# 04_-_LCD_VGA.net
KiCad netlist of a schematic drawn in Altium Designer
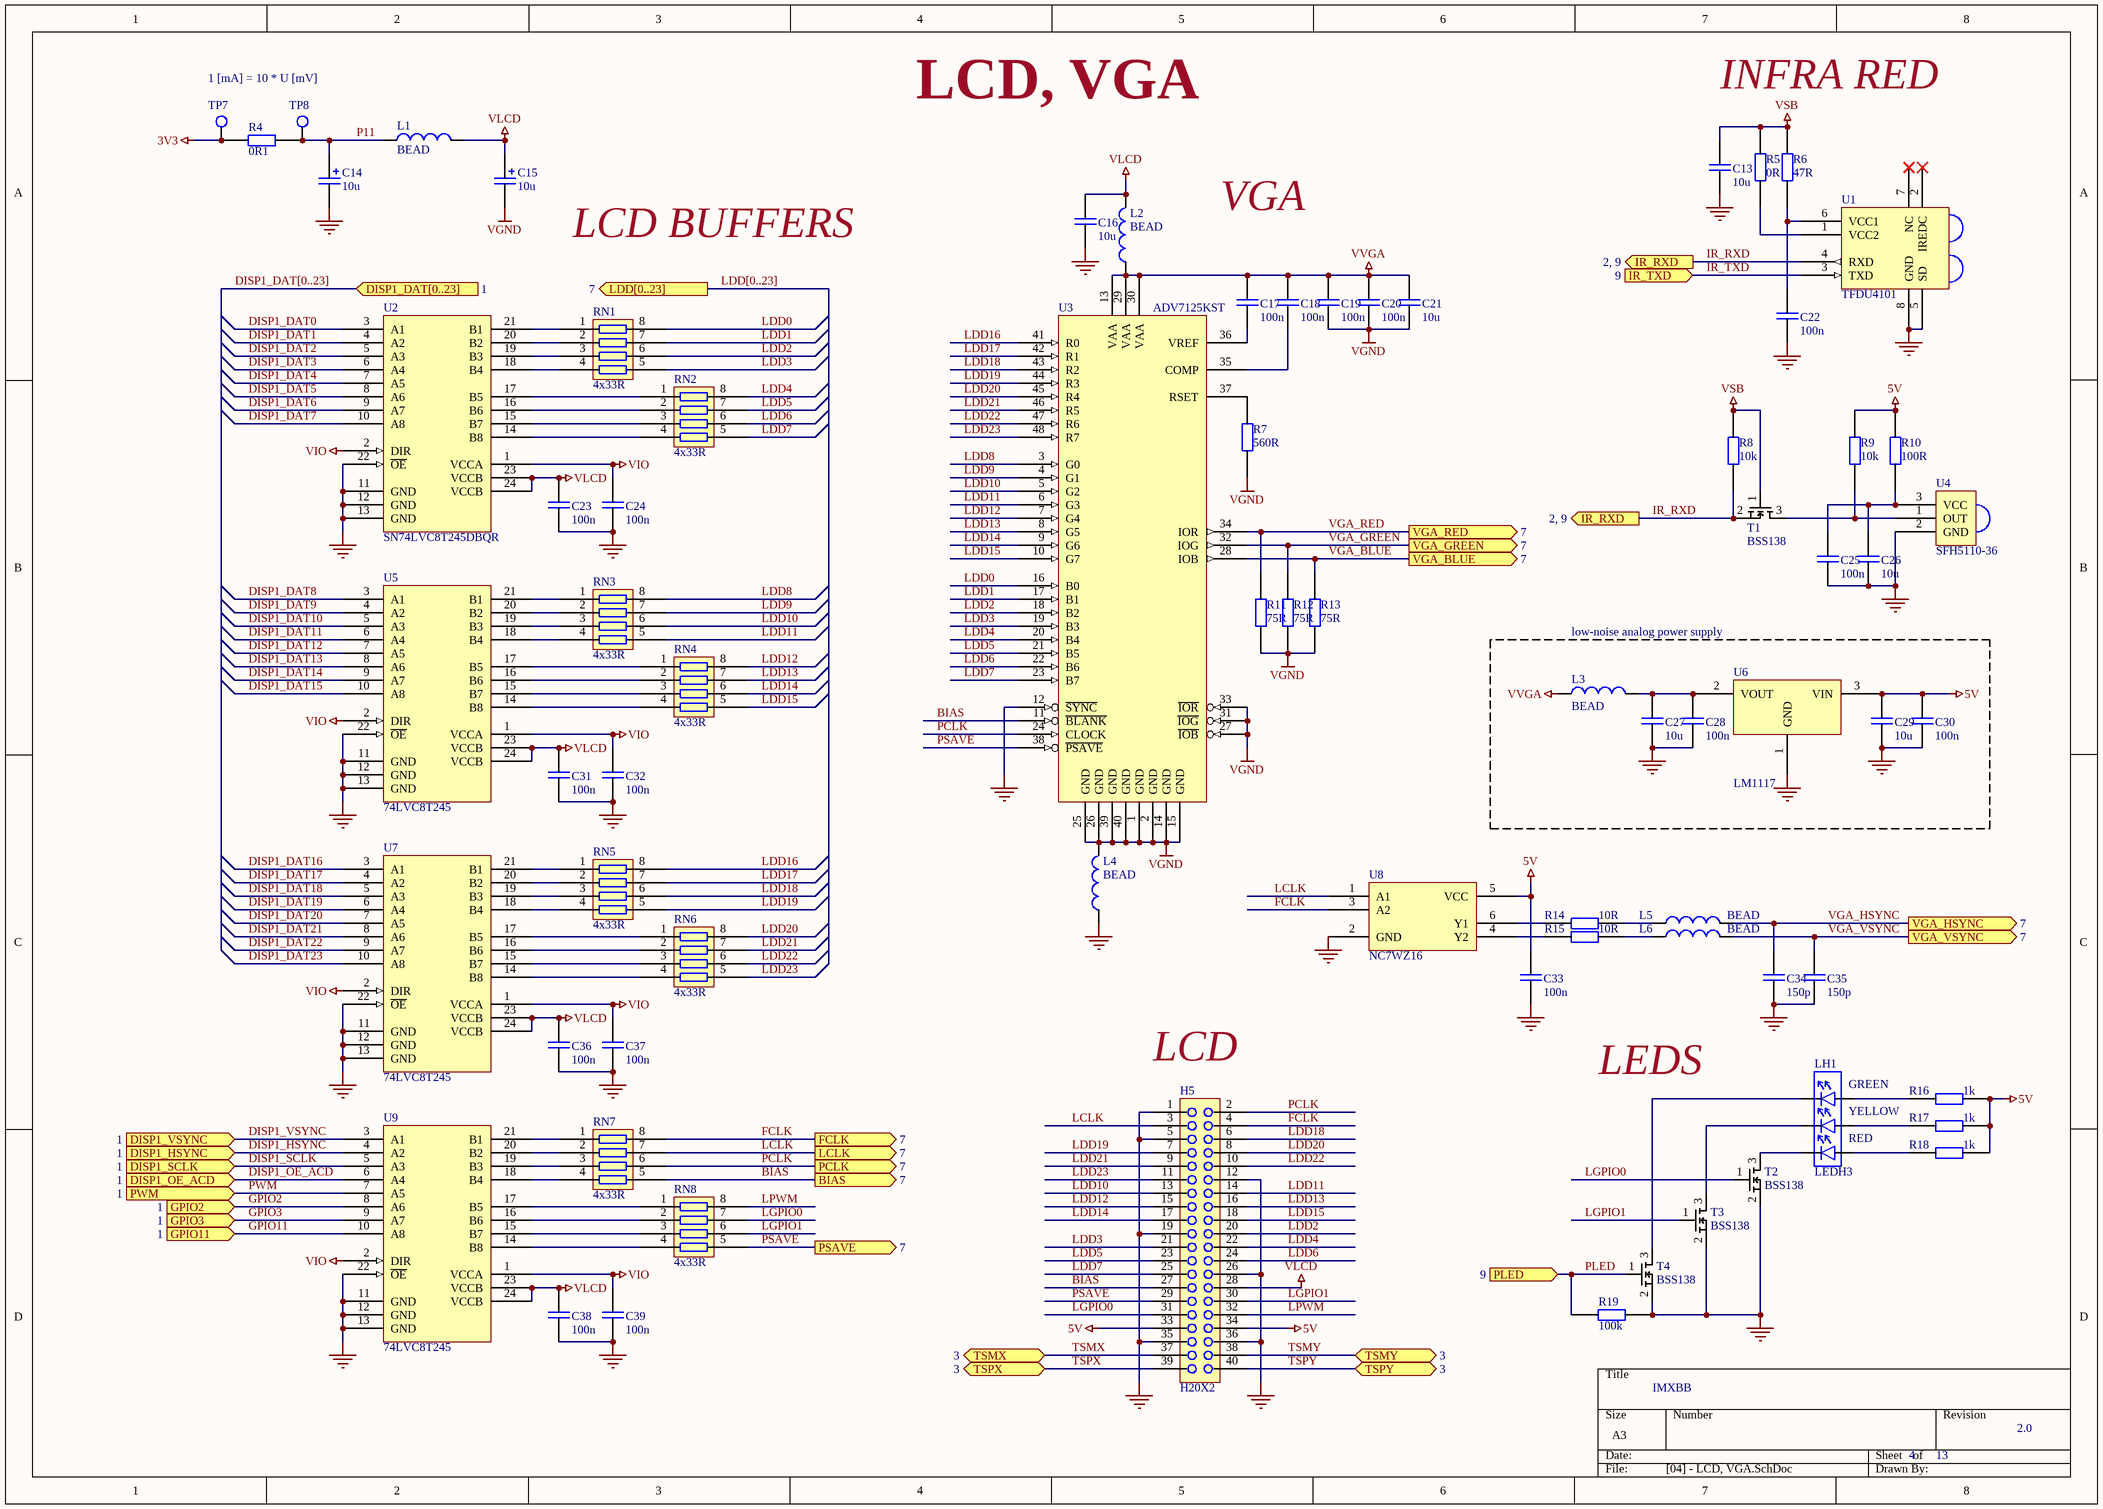
[diagram p0: [04] - LCD, VGA.SchDoc]

(export (version "E")
  (design (tool "Eeschema 10.0.6"))
  (components
    (comp (ref "C13") (value "10u") (footprint "0805") (libsource (lib "imxbb") (part "C")))
    (comp (ref "C14") (value "10u") (footprint "3216A") (libsource (lib "imxbb") (part "C+")))
    (comp (ref "C15") (value "10u") (footprint "3216A") (libsource (lib "imxbb") (part "C+")))
    (comp (ref "C16") (value "10u") (footprint "0805") (libsource (lib "imxbb") (part "C")))
    (comp (ref "C17") (value "100n") (footprint "0603") (libsource (lib "imxbb") (part "C")))
    (comp (ref "C18") (value "100n") (footprint "0603") (libsource (lib "imxbb") (part "C")))
    (comp (ref "C19") (value "100n") (footprint "0603") (libsource (lib "imxbb") (part "C")))
    (comp (ref "C20") (value "100n") (footprint "0603") (libsource (lib "imxbb") (part "C")))
    (comp (ref "C21") (value "10u") (footprint "0805") (libsource (lib "imxbb") (part "C")))
    (comp (ref "C22") (value "100n") (footprint "0603") (libsource (lib "imxbb") (part "C")))
    (comp (ref "C23") (value "100n") (footprint "0603") (libsource (lib "imxbb") (part "C")))
    (comp (ref "C24") (value "100n") (footprint "0603") (libsource (lib "imxbb") (part "C")))
    (comp (ref "C25") (value "100n") (footprint "0603") (libsource (lib "imxbb") (part "C")))
    (comp (ref "C26") (value "10u") (footprint "0805") (libsource (lib "imxbb") (part "C")))
    (comp (ref "C27") (value "10u") (footprint "0805") (libsource (lib "imxbb") (part "C")))
    (comp (ref "C28") (value "100n") (footprint "0603") (libsource (lib "imxbb") (part "C")))
    (comp (ref "C29") (value "10u") (footprint "0805") (libsource (lib "imxbb") (part "C")))
    (comp (ref "C30") (value "100n") (footprint "0603") (libsource (lib "imxbb") (part "C")))
    (comp (ref "C31") (value "100n") (footprint "0603") (libsource (lib "imxbb") (part "C")))
    (comp (ref "C32") (value "100n") (footprint "0603") (libsource (lib "imxbb") (part "C")))
    (comp (ref "C33") (value "100n") (footprint "0603") (libsource (lib "imxbb") (part "C")))
    (comp (ref "C34") (value "150p") (footprint "0603") (libsource (lib "imxbb") (part "C")))
    (comp (ref "C35") (value "150p") (footprint "0603") (libsource (lib "imxbb") (part "C")))
    (comp (ref "C36") (value "100n") (footprint "0603") (libsource (lib "imxbb") (part "C")))
    (comp (ref "C37") (value "100n") (footprint "0603") (libsource (lib "imxbb") (part "C")))
    (comp (ref "C38") (value "100n") (footprint "0603") (libsource (lib "imxbb") (part "C")))
    (comp (ref "C39") (value "100n") (footprint "0603") (libsource (lib "imxbb") (part "C")))
    (comp (ref "H5") (value "H20X2") (footprint "H2x20") (libsource (lib "imxbb") (part "H20X2")))
    (comp (ref "L1") (value "BEAD") (footprint "0603") (libsource (lib "") (part "FBEAD_1")))
    (comp (ref "L2") (value "BEAD") (footprint "0603") (libsource (lib "imxbb") (part "FBEAD")))
    (comp (ref "L3") (value "BEAD") (footprint "0603") (libsource (lib "imxbb") (part "FBEAD")))
    (comp (ref "L4") (value "BEAD") (footprint "0603") (libsource (lib "imxbb") (part "FBEAD")))
    (comp (ref "L5") (value "BEAD") (footprint "0603") (libsource (lib "imxbb") (part "FBEAD")))
    (comp (ref "L6") (value "BEAD") (footprint "0603") (libsource (lib "imxbb") (part "FBEAD")))
    (comp (ref "LH1") (value "LEDH3") (footprint "LED HOLDER 3") (libsource (lib "imxbb") (part "LEDH3")))
    (comp (ref "R4") (value "0R1") (footprint "0603") (libsource (lib "") (part "R_3")))
    (comp (ref "R5") (value "0R") (footprint "0603") (libsource (lib "") (part "R_2")))
    (comp (ref "R6") (value "47R") (footprint "0603") (libsource (lib "") (part "R_1")))
    (comp (ref "R7") (value "560R") (footprint "0603") (libsource (lib "") (part "R_2")))
    (comp (ref "R8") (value "10k") (footprint "0603") (libsource (lib "") (part "R_1")))
    (comp (ref "R9") (value "10k") (footprint "0603") (libsource (lib "") (part "R_1")))
    (comp (ref "R10") (value "100R") (footprint "0603") (libsource (lib "") (part "R_1")))
    (comp (ref "R11") (value "75R") (footprint "0603") (libsource (lib "") (part "R_2")))
    (comp (ref "R12") (value "75R") (footprint "0603") (libsource (lib "") (part "R_2")))
    (comp (ref "R13") (value "75R") (footprint "0603") (libsource (lib "") (part "R_2")))
    (comp (ref "R14") (value "10R") (footprint "0603") (libsource (lib "imxbb") (part "R")))
    (comp (ref "R15") (value "10R") (footprint "0603") (libsource (lib "imxbb") (part "R")))
    (comp (ref "R16") (value "1k") (footprint "0603") (libsource (lib "imxbb") (part "R")))
    (comp (ref "R17") (value "1k") (footprint "0603") (libsource (lib "imxbb") (part "R")))
    (comp (ref "R18") (value "1k") (footprint "0603") (libsource (lib "imxbb") (part "R")))
    (comp (ref "R19") (value "100k") (footprint "0603") (libsource (lib "") (part "R_3")))
    (comp (ref "RN1") (value "4x33R") (footprint "RX4_NS") (libsource (lib "imxbb") (part "RN4")))
    (comp (ref "RN2") (value "4x33R") (footprint "RX4_NS") (libsource (lib "imxbb") (part "RN4")))
    (comp (ref "RN3") (value "4x33R") (footprint "RX4_NS") (libsource (lib "imxbb") (part "RN4")))
    (comp (ref "RN4") (value "4x33R") (footprint "RX4_NS") (libsource (lib "imxbb") (part "RN4")))
    (comp (ref "RN5") (value "4x33R") (footprint "RX4_NS") (libsource (lib "imxbb") (part "RN4")))
    (comp (ref "RN6") (value "4x33R") (footprint "RX4_NS") (libsource (lib "imxbb") (part "RN4")))
    (comp (ref "RN7") (value "4x33R") (footprint "RX4_NS") (libsource (lib "imxbb") (part "RN4")))
    (comp (ref "RN8") (value "4x33R") (footprint "RX4_NS") (libsource (lib "imxbb") (part "RN4")))
    (comp (ref "T1") (value "BSS138") (footprint "SOT23") (libsource (lib "imxbb") (part "BSS138")))
    (comp (ref "T2") (value "BSS138") (footprint "SOT23") (libsource (lib "imxbb") (part "BSS138")))
    (comp (ref "T3") (value "BSS138") (footprint "SOT23") (libsource (lib "imxbb") (part "BSS138")))
    (comp (ref "T4") (value "BSS138") (footprint "SOT23") (libsource (lib "imxbb") (part "BSS138")))
    (comp (ref "TP7")
      (value "TESTPOINT")
      (footprint "TESTPOINT_2mm")
      (description "Testpoint pad")
      (libsource (lib "imxbb") (part "TESTPOINT"))
    )
    (comp (ref "TP8")
      (value "TESTPOINT")
      (footprint "TESTPOINT_2mm")
      (description "Testpoint pad")
      (libsource (lib "imxbb") (part "TESTPOINT"))
    )
    (comp (ref "U1") (value "TFDU4101") (footprint "TDFU4101") (libsource (lib "imxbb") (part "TFDU4101")))
    (comp (ref "U2")
      (value "SN74LVC8T245DBQR")
      (description "IC BUS TRANSCVR 8BIT 24QSOP")
      (fields (field (name "MANUFACTURER") "Texas Instruments"))
      (libsource (lib "MyLibrary") (part "SN74LVC8T245DBQR"))
    )
    (comp (ref "U3") (value "ADV7125KST") (footprint "LQFP48") (libsource (lib "imxbb") (part "ADV7125")))
    (comp (ref "U4") (value "SFH5110-36") (footprint "SFH511x") (libsource (lib "imxbb") (part "SFH5110")))
    (comp (ref "U5") (value "74LVC8T245") (footprint "TSSOP24") (libsource (lib "imxbb") (part "74LVC8T245")))
    (comp (ref "U6") (value "LM1117") (footprint "SOT223") (libsource (lib "imxbb") (part "LM1117")))
    (comp (ref "U7") (value "74LVC8T245") (footprint "TSSOP24") (libsource (lib "imxbb") (part "74LVC8T245")))
    (comp (ref "U8") (value "NC7WZ16") (footprint "SC70") (libsource (lib "imxbb") (part "NC7WZ16")))
    (comp (ref "U9") (value "74LVC8T245") (footprint "TSSOP24") (libsource (lib "imxbb") (part "74LVC8T245")))
  )
  (nets
    (net (code "1") (name "/BIAS") (class "Default")
      (node (ref "H5") (pin "27") (pinfunction "27_27") (pintype "passive"))
      (node (ref "RN7") (pin "5") (pintype "passive"))
      (node (ref "U3") (pin "11") (pinfunction "~{BLANK}_11") (pintype "input"))
    )
    (net (code "2") (name "/DISP1_DAT0") (class "Default")
      (node (ref "U2") (pin "3") (pinfunction "A1_3") (pintype "passive"))
    )
    (net (code "3") (name "/DISP1_DAT1") (class "Default")
      (node (ref "U2") (pin "4") (pinfunction "A2_4") (pintype "passive"))
    )
    (net (code "4") (name "/DISP1_DAT2") (class "Default")
      (node (ref "U2") (pin "5") (pinfunction "A3_5") (pintype "passive"))
    )
    (net (code "5") (name "/DISP1_DAT3") (class "Default")
      (node (ref "U2") (pin "6") (pinfunction "A4_6") (pintype "passive"))
    )
    (net (code "6") (name "/DISP1_DAT4") (class "Default")
      (node (ref "U2") (pin "7") (pinfunction "A5_7") (pintype "passive"))
    )
    (net (code "7") (name "/DISP1_DAT5") (class "Default")
      (node (ref "U2") (pin "8") (pinfunction "A6_8") (pintype "passive"))
    )
    (net (code "8") (name "/DISP1_DAT6") (class "Default")
      (node (ref "U2") (pin "9") (pinfunction "A7_9") (pintype "passive"))
    )
    (net (code "9") (name "/DISP1_DAT7") (class "Default")
      (node (ref "U2") (pin "10") (pinfunction "A8_10") (pintype "passive"))
    )
    (net (code "10") (name "/DISP1_DAT8") (class "Default")
      (node (ref "U5") (pin "3") (pinfunction "A1_3") (pintype "passive"))
    )
    (net (code "11") (name "/DISP1_DAT9") (class "Default")
      (node (ref "U5") (pin "4") (pinfunction "A2_4") (pintype "passive"))
    )
    (net (code "12") (name "/DISP1_DAT10") (class "Default")
      (node (ref "U5") (pin "5") (pinfunction "A3_5") (pintype "passive"))
    )
    (net (code "13") (name "/DISP1_DAT11") (class "Default")
      (node (ref "U5") (pin "6") (pinfunction "A4_6") (pintype "passive"))
    )
    (net (code "14") (name "/DISP1_DAT12") (class "Default")
      (node (ref "U5") (pin "7") (pinfunction "A5_7") (pintype "passive"))
    )
    (net (code "15") (name "/DISP1_DAT13") (class "Default")
      (node (ref "U5") (pin "8") (pinfunction "A6_8") (pintype "passive"))
    )
    (net (code "16") (name "/DISP1_DAT14") (class "Default")
      (node (ref "U5") (pin "9") (pinfunction "A7_9") (pintype "passive"))
    )
    (net (code "17") (name "/DISP1_DAT15") (class "Default")
      (node (ref "U5") (pin "10") (pinfunction "A8_10") (pintype "passive"))
    )
    (net (code "18") (name "/DISP1_DAT16") (class "Default")
      (node (ref "U7") (pin "3") (pinfunction "A1_3") (pintype "passive"))
    )
    (net (code "19") (name "/DISP1_DAT17") (class "Default")
      (node (ref "U7") (pin "4") (pinfunction "A2_4") (pintype "passive"))
    )
    (net (code "20") (name "/DISP1_DAT18") (class "Default")
      (node (ref "U7") (pin "5") (pinfunction "A3_5") (pintype "passive"))
    )
    (net (code "21") (name "/DISP1_DAT19") (class "Default")
      (node (ref "U7") (pin "6") (pinfunction "A4_6") (pintype "passive"))
    )
    (net (code "22") (name "/DISP1_DAT20") (class "Default")
      (node (ref "U7") (pin "7") (pinfunction "A5_7") (pintype "passive"))
    )
    (net (code "23") (name "/DISP1_DAT21") (class "Default")
      (node (ref "U7") (pin "8") (pinfunction "A6_8") (pintype "passive"))
    )
    (net (code "24") (name "/DISP1_DAT22") (class "Default")
      (node (ref "U7") (pin "9") (pinfunction "A7_9") (pintype "passive"))
    )
    (net (code "25") (name "/DISP1_DAT23") (class "Default")
      (node (ref "U7") (pin "10") (pinfunction "A8_10") (pintype "passive"))
    )
    (net (code "27") (name "/DISP1_HSYNC") (class "Default")
      (node (ref "U9") (pin "4") (pinfunction "A2_4") (pintype "passive"))
    )
    (net (code "28") (name "/DISP1_OE_ACD") (class "Default")
      (node (ref "U9") (pin "6") (pinfunction "A4_6") (pintype "passive"))
    )
    (net (code "29") (name "/DISP1_SCLK") (class "Default")
      (node (ref "U9") (pin "5") (pinfunction "A3_5") (pintype "passive"))
    )
    (net (code "30") (name "/DISP1_VSYNC") (class "Default")
      (node (ref "U9") (pin "3") (pinfunction "A1_3") (pintype "passive"))
    )
    (net (code "31") (name "/FCLK") (class "Default")
      (node (ref "H5") (pin "4") (pinfunction "4_4") (pintype "passive"))
      (node (ref "RN7") (pin "8") (pintype "passive"))
      (node (ref "U8") (pin "3") (pinfunction "A2_3") (pintype "passive"))
    )
    (net (code "32") (name "/GPIO2") (class "Default")
      (node (ref "U9") (pin "8") (pinfunction "A6_8") (pintype "passive"))
    )
    (net (code "33") (name "/GPIO3") (class "Default")
      (node (ref "U9") (pin "9") (pinfunction "A7_9") (pintype "passive"))
    )
    (net (code "34") (name "/GPIO11") (class "Default")
      (node (ref "U9") (pin "10") (pinfunction "A8_10") (pintype "passive"))
    )
    (net (code "35") (name "/IR_RXD") (class "Default")
      (node (ref "R8") (pin "2") (pinfunction "2_2") (pintype "passive"))
      (node (ref "T1") (pin "2") (pinfunction "S_2") (pintype "passive"))
      (node (ref "U1") (pin "4") (pinfunction "RXD_4") (pintype "output"))
    )
    (net (code "36") (name "/IR_TXD") (class "Default")
      (node (ref "U1") (pin "3") (pinfunction "TXD_3") (pintype "input"))
    )
    (net (code "37") (name "/LCLK") (class "Default")
      (node (ref "H5") (pin "3") (pinfunction "3_3") (pintype "passive"))
      (node (ref "RN7") (pin "7") (pintype "passive"))
      (node (ref "U8") (pin "1") (pinfunction "A1_1") (pintype "passive"))
    )
    (net (code "38") (name "/LDD0") (class "Default")
      (node (ref "RN1") (pin "8") (pintype "passive"))
      (node (ref "U3") (pin "16") (pinfunction "B0_16") (pintype "input"))
    )
    (net (code "39") (name "/LDD1") (class "Default")
      (node (ref "RN1") (pin "7") (pintype "passive"))
      (node (ref "U3") (pin "17") (pinfunction "B1_17") (pintype "input"))
    )
    (net (code "40") (name "/LDD2") (class "Default")
      (node (ref "H5") (pin "20") (pinfunction "20_20") (pintype "passive"))
      (node (ref "RN1") (pin "6") (pintype "passive"))
      (node (ref "U3") (pin "18") (pinfunction "B2_18") (pintype "input"))
    )
    (net (code "41") (name "/LDD3") (class "Default")
      (node (ref "H5") (pin "21") (pinfunction "21_21") (pintype "passive"))
      (node (ref "RN1") (pin "5") (pintype "passive"))
      (node (ref "U3") (pin "19") (pinfunction "B3_19") (pintype "input"))
    )
    (net (code "42") (name "/LDD4") (class "Default")
      (node (ref "H5") (pin "22") (pinfunction "22_22") (pintype "passive"))
      (node (ref "RN2") (pin "8") (pintype "passive"))
      (node (ref "U3") (pin "20") (pinfunction "B4_20") (pintype "input"))
    )
    (net (code "43") (name "/LDD5") (class "Default")
      (node (ref "H5") (pin "23") (pinfunction "23_23") (pintype "passive"))
      (node (ref "RN2") (pin "7") (pintype "passive"))
      (node (ref "U3") (pin "21") (pinfunction "B5_21") (pintype "input"))
    )
    (net (code "44") (name "/LDD6") (class "Default")
      (node (ref "H5") (pin "24") (pinfunction "24_24") (pintype "passive"))
      (node (ref "RN2") (pin "6") (pintype "passive"))
      (node (ref "U3") (pin "22") (pinfunction "B6_22") (pintype "input"))
    )
    (net (code "45") (name "/LDD7") (class "Default")
      (node (ref "H5") (pin "25") (pinfunction "25_25") (pintype "passive"))
      (node (ref "RN2") (pin "5") (pintype "passive"))
      (node (ref "U3") (pin "23") (pinfunction "B7_23") (pintype "input"))
    )
    (net (code "46") (name "/LDD8") (class "Default")
      (node (ref "RN3") (pin "8") (pintype "passive"))
      (node (ref "U3") (pin "3") (pinfunction "G0_3") (pintype "input"))
    )
    (net (code "47") (name "/LDD9") (class "Default")
      (node (ref "RN3") (pin "7") (pintype "passive"))
      (node (ref "U3") (pin "4") (pinfunction "G1_4") (pintype "input"))
    )
    (net (code "48") (name "/LDD10") (class "Default")
      (node (ref "H5") (pin "13") (pinfunction "13_13") (pintype "passive"))
      (node (ref "RN3") (pin "6") (pintype "passive"))
      (node (ref "U3") (pin "5") (pinfunction "G2_5") (pintype "input"))
    )
    (net (code "49") (name "/LDD11") (class "Default")
      (node (ref "H5") (pin "14") (pinfunction "14_14") (pintype "passive"))
      (node (ref "RN3") (pin "5") (pintype "passive"))
      (node (ref "U3") (pin "6") (pinfunction "G3_6") (pintype "input"))
    )
    (net (code "50") (name "/LDD12") (class "Default")
      (node (ref "H5") (pin "15") (pinfunction "15_15") (pintype "passive"))
      (node (ref "RN4") (pin "8") (pintype "passive"))
      (node (ref "U3") (pin "7") (pinfunction "G4_7") (pintype "input"))
    )
    (net (code "51") (name "/LDD13") (class "Default")
      (node (ref "H5") (pin "16") (pinfunction "16_16") (pintype "passive"))
      (node (ref "RN4") (pin "7") (pintype "passive"))
      (node (ref "U3") (pin "8") (pinfunction "G5_8") (pintype "input"))
    )
    (net (code "52") (name "/LDD14") (class "Default")
      (node (ref "H5") (pin "17") (pinfunction "17_17") (pintype "passive"))
      (node (ref "RN4") (pin "6") (pintype "passive"))
      (node (ref "U3") (pin "9") (pinfunction "G6_9") (pintype "input"))
    )
    (net (code "53") (name "/LDD15") (class "Default")
      (node (ref "H5") (pin "18") (pinfunction "18_18") (pintype "passive"))
      (node (ref "RN4") (pin "5") (pintype "passive"))
      (node (ref "U3") (pin "10") (pinfunction "G7_10") (pintype "input"))
    )
    (net (code "54") (name "/LDD16") (class "Default")
      (node (ref "RN5") (pin "8") (pintype "passive"))
      (node (ref "U3") (pin "41") (pinfunction "R0_41") (pintype "input"))
    )
    (net (code "55") (name "/LDD17") (class "Default")
      (node (ref "RN5") (pin "7") (pintype "passive"))
      (node (ref "U3") (pin "42") (pinfunction "R1_42") (pintype "input"))
    )
    (net (code "56") (name "/LDD18") (class "Default")
      (node (ref "H5") (pin "6") (pinfunction "6_6") (pintype "passive"))
      (node (ref "RN5") (pin "6") (pintype "passive"))
      (node (ref "U3") (pin "43") (pinfunction "R2_43") (pintype "input"))
    )
    (net (code "57") (name "/LDD19") (class "Default")
      (node (ref "H5") (pin "7") (pinfunction "7_7") (pintype "passive"))
      (node (ref "RN5") (pin "5") (pintype "passive"))
      (node (ref "U3") (pin "44") (pinfunction "R3_44") (pintype "input"))
    )
    (net (code "58") (name "/LDD20") (class "Default")
      (node (ref "H5") (pin "8") (pinfunction "8_8") (pintype "passive"))
      (node (ref "RN6") (pin "8") (pintype "passive"))
      (node (ref "U3") (pin "45") (pinfunction "R4_45") (pintype "input"))
    )
    (net (code "59") (name "/LDD21") (class "Default")
      (node (ref "H5") (pin "9") (pinfunction "9_9") (pintype "passive"))
      (node (ref "RN6") (pin "7") (pintype "passive"))
      (node (ref "U3") (pin "46") (pinfunction "R5_46") (pintype "input"))
    )
    (net (code "60") (name "/LDD22") (class "Default")
      (node (ref "H5") (pin "10") (pinfunction "10_10") (pintype "passive"))
      (node (ref "RN6") (pin "6") (pintype "passive"))
      (node (ref "U3") (pin "47") (pinfunction "R6_47") (pintype "input"))
    )
    (net (code "61") (name "/LDD23") (class "Default")
      (node (ref "H5") (pin "11") (pinfunction "11_11") (pintype "passive"))
      (node (ref "RN6") (pin "5") (pintype "passive"))
      (node (ref "U3") (pin "48") (pinfunction "R7_48") (pintype "input"))
    )
    (net (code "63") (name "/LGPIO0") (class "Default")
      (node (ref "H5") (pin "31") (pinfunction "31_31") (pintype "passive"))
      (node (ref "RN8") (pin "7") (pintype "passive"))
      (node (ref "T2") (pin "1") (pinfunction "G_1") (pintype "passive"))
    )
    (net (code "64") (name "/LGPIO1") (class "Default")
      (node (ref "H5") (pin "30") (pinfunction "30_30") (pintype "passive"))
      (node (ref "RN8") (pin "6") (pintype "passive"))
      (node (ref "T3") (pin "1") (pinfunction "G_1") (pintype "passive"))
    )
    (net (code "65") (name "/LPWM") (class "Default")
      (node (ref "H5") (pin "32") (pinfunction "32_32") (pintype "passive"))
      (node (ref "RN8") (pin "8") (pintype "passive"))
    )
    (net (code "66") (name "/P11") (class "Default")
      (node (ref "C14") (pin "1") (pinfunction "1_1") (pintype "passive"))
      (node (ref "L1") (pin "2") (pinfunction "2_2") (pintype "passive"))
      (node (ref "R4") (pin "2") (pinfunction "2_2") (pintype "passive"))
      (node (ref "TP8") (pin "1") (pinfunction "1_1") (pintype "passive"))
    )
    (net (code "67") (name "/PCLK") (class "Default")
      (node (ref "H5") (pin "2") (pinfunction "2_2") (pintype "passive"))
      (node (ref "RN7") (pin "6") (pintype "passive"))
      (node (ref "U3") (pin "24") (pinfunction "CLOCK_24") (pintype "input"))
    )
    (net (code "68") (name "/PLED") (class "Default")
      (node (ref "R19") (pin "1") (pinfunction "1_1") (pintype "passive"))
      (node (ref "T4") (pin "1") (pinfunction "G_1") (pintype "passive"))
    )
    (net (code "69") (name "/PSAVE") (class "Default")
      (node (ref "H5") (pin "29") (pinfunction "29_29") (pintype "passive"))
      (node (ref "RN8") (pin "5") (pintype "passive"))
      (node (ref "U3") (pin "38") (pinfunction "~{PSAVE}_38") (pintype "input"))
    )
    (net (code "70") (name "/PWM") (class "Default")
      (node (ref "U9") (pin "7") (pinfunction "A5_7") (pintype "passive"))
    )
    (net (code "71") (name "/TSMX") (class "Default")
      (node (ref "H5") (pin "37") (pinfunction "37_37") (pintype "passive"))
    )
    (net (code "72") (name "/TSMY") (class "Default")
      (node (ref "H5") (pin "38") (pinfunction "38_38") (pintype "passive"))
    )
    (net (code "73") (name "/TSPX") (class "Default")
      (node (ref "H5") (pin "39") (pinfunction "39_39") (pintype "passive"))
    )
    (net (code "74") (name "/TSPY") (class "Default")
      (node (ref "H5") (pin "40") (pinfunction "40_40") (pintype "passive"))
    )
    (net (code "75") (name "/VGA_BLUE") (class "Default")
      (node (ref "R13") (pin "2") (pinfunction "2_2") (pintype "passive"))
      (node (ref "U3") (pin "28") (pinfunction "IOB_28") (pintype "output"))
    )
    (net (code "76") (name "/VGA_GREEN") (class "Default")
      (node (ref "R12") (pin "2") (pinfunction "2_2") (pintype "passive"))
      (node (ref "U3") (pin "32") (pinfunction "IOG_32") (pintype "output"))
    )
    (net (code "77") (name "/VGA_HSYNC") (class "Default")
      (node (ref "C34") (pin "2") (pinfunction "2_2") (pintype "passive"))
      (node (ref "L5") (pin "2") (pinfunction "2_2") (pintype "passive"))
    )
    (net (code "78") (name "/VGA_RED") (class "Default")
      (node (ref "R11") (pin "2") (pinfunction "2_2") (pintype "passive"))
      (node (ref "U3") (pin "34") (pinfunction "IOR_34") (pintype "output"))
    )
    (net (code "79") (name "/VGA_VSYNC") (class "Default")
      (node (ref "C35") (pin "2") (pinfunction "2_2") (pintype "passive"))
      (node (ref "L6") (pin "2") (pinfunction "2_2") (pintype "passive"))
    )
    (net (code "80") (name "3V3") (class "Default")
      (node (ref "R4") (pin "1") (pinfunction "1_1") (pintype "passive"))
      (node (ref "TP7") (pin "1") (pinfunction "1_1") (pintype "passive"))
    )
    (net (code "81") (name "5V") (class "Default")
      (node (ref "C29") (pin "2") (pinfunction "2_2") (pintype "passive"))
      (node (ref "C30") (pin "2") (pinfunction "2_2") (pintype "passive"))
      (node (ref "C33") (pin "2") (pinfunction "2_2") (pintype "passive"))
      (node (ref "H5") (pin "33") (pinfunction "33_33") (pintype "passive"))
      (node (ref "H5") (pin "34") (pinfunction "34_34") (pintype "passive"))
      (node (ref "R10") (pin "1") (pinfunction "1_1") (pintype "passive"))
      (node (ref "R16") (pin "1") (pinfunction "1_1") (pintype "passive"))
      (node (ref "R17") (pin "1") (pinfunction "1_1") (pintype "passive"))
      (node (ref "R18") (pin "1") (pinfunction "1_1") (pintype "passive"))
      (node (ref "R9") (pin "1") (pinfunction "1_1") (pintype "passive"))
      (node (ref "U6") (pin "3") (pinfunction "VIN_3") (pintype "passive"))
      (node (ref "U8") (pin "5") (pinfunction "VCC_5") (pintype "passive"))
    )
    (net (code "82") (name "GND") (class "Default")
      (node (ref "C13") (pin "1") (pinfunction "1_1") (pintype "passive"))
      (node (ref "C14") (pin "2") (pinfunction "2_2") (pintype "passive"))
      (node (ref "C16") (pin "1") (pinfunction "1_1") (pintype "passive"))
      (node (ref "C22") (pin "1") (pinfunction "1_1") (pintype "passive"))
      (node (ref "C23") (pin "1") (pinfunction "1_1") (pintype "passive"))
      (node (ref "C24") (pin "1") (pinfunction "1_1") (pintype "passive"))
      (node (ref "C25") (pin "1") (pinfunction "1_1") (pintype "passive"))
      (node (ref "C26") (pin "1") (pinfunction "1_1") (pintype "passive"))
      (node (ref "C27") (pin "1") (pinfunction "1_1") (pintype "passive"))
      (node (ref "C28") (pin "1") (pinfunction "1_1") (pintype "passive"))
      (node (ref "C29") (pin "1") (pinfunction "1_1") (pintype "passive"))
      (node (ref "C30") (pin "1") (pinfunction "1_1") (pintype "passive"))
      (node (ref "C31") (pin "1") (pinfunction "1_1") (pintype "passive"))
      (node (ref "C32") (pin "1") (pinfunction "1_1") (pintype "passive"))
      (node (ref "C33") (pin "1") (pinfunction "1_1") (pintype "passive"))
      (node (ref "C34") (pin "1") (pinfunction "1_1") (pintype "passive"))
      (node (ref "C35") (pin "1") (pinfunction "1_1") (pintype "passive"))
      (node (ref "C36") (pin "1") (pinfunction "1_1") (pintype "passive"))
      (node (ref "C37") (pin "1") (pinfunction "1_1") (pintype "passive"))
      (node (ref "C38") (pin "1") (pinfunction "1_1") (pintype "passive"))
      (node (ref "C39") (pin "1") (pinfunction "1_1") (pintype "passive"))
      (node (ref "H5") (pin "1") (pinfunction "1_1") (pintype "passive"))
      (node (ref "H5") (pin "12") (pinfunction "12_12") (pintype "passive"))
      (node (ref "H5") (pin "19") (pinfunction "19_19") (pintype "passive"))
      (node (ref "H5") (pin "26") (pinfunction "26_26") (pintype "passive"))
      (node (ref "H5") (pin "35") (pinfunction "35_35") (pintype "passive"))
      (node (ref "H5") (pin "36") (pinfunction "36_36") (pintype "passive"))
      (node (ref "H5") (pin "5") (pinfunction "5_5") (pintype "passive"))
      (node (ref "L4") (pin "1") (pinfunction "1_1") (pintype "passive"))
      (node (ref "R19") (pin "2") (pinfunction "2_2") (pintype "passive"))
      (node (ref "T2") (pin "2") (pinfunction "S_2") (pintype "passive"))
      (node (ref "T3") (pin "2") (pinfunction "S_2") (pintype "passive"))
      (node (ref "T4") (pin "2") (pinfunction "S_2") (pintype "passive"))
      (node (ref "U1") (pin "5") (pinfunction "SD_5") (pintype "passive"))
      (node (ref "U1") (pin "8") (pinfunction "GND_8") (pintype "passive"))
      (node (ref "U2") (pin "11") (pinfunction "GND_11") (pintype "power_in"))
      (node (ref "U2") (pin "12") (pinfunction "GND_12") (pintype "power_in"))
      (node (ref "U2") (pin "13") (pinfunction "GND_13") (pintype "power_in"))
      (node (ref "U2") (pin "22") (pinfunction "~{OE}_22") (pintype "input"))
      (node (ref "U3") (pin "12") (pinfunction "~{SYNC}_12") (pintype "input"))
      (node (ref "U4") (pin "2") (pinfunction "GND_2") (pintype "passive"))
      (node (ref "U5") (pin "11") (pinfunction "GND_11") (pintype "power_in"))
      (node (ref "U5") (pin "12") (pinfunction "GND_12") (pintype "power_in"))
      (node (ref "U5") (pin "13") (pinfunction "GND_13") (pintype "power_in"))
      (node (ref "U5") (pin "22") (pinfunction "~{OE}_22") (pintype "input"))
      (node (ref "U6") (pin "1") (pinfunction "GND_1") (pintype "passive"))
      (node (ref "U7") (pin "11") (pinfunction "GND_11") (pintype "power_in"))
      (node (ref "U7") (pin "12") (pinfunction "GND_12") (pintype "power_in"))
      (node (ref "U7") (pin "13") (pinfunction "GND_13") (pintype "power_in"))
      (node (ref "U7") (pin "22") (pinfunction "~{OE}_22") (pintype "input"))
      (node (ref "U8") (pin "2") (pinfunction "GND_2") (pintype "passive"))
      (node (ref "U9") (pin "11") (pinfunction "GND_11") (pintype "power_in"))
      (node (ref "U9") (pin "12") (pinfunction "GND_12") (pintype "power_in"))
      (node (ref "U9") (pin "13") (pinfunction "GND_13") (pintype "power_in"))
      (node (ref "U9") (pin "22") (pinfunction "~{OE}_22") (pintype "input"))
    )
    (net (code "83") (name "Net-(L5-Pad1)") (class "Default")
      (node (ref "L5") (pin "1") (pinfunction "1_1") (pintype "passive"))
      (node (ref "R14") (pin "1") (pinfunction "1_1") (pintype "passive"))
    )
    (net (code "84") (name "Net-(L6-Pad1)") (class "Default")
      (node (ref "L6") (pin "1") (pinfunction "1_1") (pintype "passive"))
      (node (ref "R15") (pin "1") (pinfunction "1_1") (pintype "passive"))
    )
    (net (code "85") (name "Net-(LH1-Pad2)") (class "Default")
      (node (ref "LH1") (pin "2") (pinfunction "2_2") (pintype "passive"))
      (node (ref "R16") (pin "2") (pinfunction "2_2") (pintype "passive"))
    )
    (net (code "86") (name "Net-(LH1-Pad4)") (class "Default")
      (node (ref "LH1") (pin "4") (pinfunction "4_4") (pintype "passive"))
      (node (ref "R17") (pin "2") (pinfunction "2_2") (pintype "passive"))
    )
    (net (code "87") (name "Net-(LH1-Pad6)") (class "Default")
      (node (ref "LH1") (pin "6") (pinfunction "6_6") (pintype "passive"))
      (node (ref "R18") (pin "2") (pinfunction "2_2") (pintype "passive"))
    )
    (net (code "88") (name "Net-(T1-D)") (class "Default")
      (node (ref "R9") (pin "2") (pinfunction "2_2") (pintype "passive"))
      (node (ref "T1") (pin "3") (pinfunction "D_3") (pintype "passive"))
      (node (ref "U4") (pin "1") (pinfunction "OUT_1") (pintype "passive"))
    )
    (net (code "89") (name "Net-(T2-D)") (class "Default")
      (node (ref "LH1") (pin "5") (pinfunction "5_5") (pintype "passive"))
      (node (ref "T2") (pin "3") (pinfunction "D_3") (pintype "passive"))
    )
    (net (code "90") (name "Net-(T3-D)") (class "Default")
      (node (ref "LH1") (pin "3") (pinfunction "3_3") (pintype "passive"))
      (node (ref "T3") (pin "3") (pinfunction "D_3") (pintype "passive"))
    )
    (net (code "91") (name "Net-(T4-D)") (class "Default")
      (node (ref "LH1") (pin "1") (pinfunction "1_1") (pintype "passive"))
      (node (ref "T4") (pin "3") (pinfunction "D_3") (pintype "passive"))
    )
    (net (code "92") (name "Net-(U1-VCC1)") (class "Default")
      (node (ref "C22") (pin "2") (pinfunction "2_2") (pintype "passive"))
      (node (ref "R6") (pin "2") (pinfunction "2_2") (pintype "passive"))
      (node (ref "U1") (pin "6") (pinfunction "VCC1_6") (pintype "passive"))
    )
    (net (code "93") (name "Net-(U1-VCC2)") (class "Default")
      (node (ref "R5") (pin "1") (pinfunction "1_1") (pintype "passive"))
      (node (ref "U1") (pin "1") (pinfunction "VCC2_1") (pintype "passive"))
    )
    (net (code "94") (name "Net-(U2-B1)") (class "Default")
      (node (ref "RN1") (pin "1") (pintype "passive"))
      (node (ref "U2") (pin "21") (pinfunction "B1_21") (pintype "passive"))
    )
    (net (code "95") (name "Net-(U2-B2)") (class "Default")
      (node (ref "RN1") (pin "2") (pintype "passive"))
      (node (ref "U2") (pin "20") (pinfunction "B2_20") (pintype "passive"))
    )
    (net (code "96") (name "Net-(U2-B3)") (class "Default")
      (node (ref "RN1") (pin "3") (pintype "passive"))
      (node (ref "U2") (pin "19") (pinfunction "B3_19") (pintype "passive"))
    )
    (net (code "97") (name "Net-(U2-B4)") (class "Default")
      (node (ref "RN1") (pin "4") (pintype "passive"))
      (node (ref "U2") (pin "18") (pinfunction "B4_18") (pintype "passive"))
    )
    (net (code "98") (name "Net-(U2-B5)") (class "Default")
      (node (ref "RN2") (pin "1") (pintype "passive"))
      (node (ref "U2") (pin "17") (pinfunction "B5_17") (pintype "passive"))
    )
    (net (code "99") (name "Net-(U2-B6)") (class "Default")
      (node (ref "RN2") (pin "2") (pintype "passive"))
      (node (ref "U2") (pin "16") (pinfunction "B6_16") (pintype "passive"))
    )
    (net (code "100") (name "Net-(U2-B7)") (class "Default")
      (node (ref "RN2") (pin "3") (pintype "passive"))
      (node (ref "U2") (pin "15") (pinfunction "B7_15") (pintype "passive"))
    )
    (net (code "101") (name "Net-(U2-B8)") (class "Default")
      (node (ref "RN2") (pin "4") (pintype "passive"))
      (node (ref "U2") (pin "14") (pinfunction "B8_14") (pintype "passive"))
    )
    (net (code "102") (name "Net-(U3-COMP)") (class "Default")
      (node (ref "C18") (pin "1") (pinfunction "1_1") (pintype "passive"))
      (node (ref "U3") (pin "35") (pinfunction "COMP_35") (pintype "passive"))
    )
    (net (code "103") (name "Net-(U3-RSET)") (class "Default")
      (node (ref "R7") (pin "2") (pinfunction "2_2") (pintype "passive"))
      (node (ref "U3") (pin "37") (pinfunction "RSET_37") (pintype "passive"))
    )
    (net (code "104") (name "Net-(U3-VREF)") (class "Default")
      (node (ref "C17") (pin "1") (pinfunction "1_1") (pintype "passive"))
      (node (ref "U3") (pin "36") (pinfunction "VREF_36") (pintype "passive"))
    )
    (net (code "105") (name "Net-(U4-VCC)") (class "Default")
      (node (ref "C25") (pin "2") (pinfunction "2_2") (pintype "passive"))
      (node (ref "C26") (pin "2") (pinfunction "2_2") (pintype "passive"))
      (node (ref "R10") (pin "2") (pinfunction "2_2") (pintype "passive"))
      (node (ref "U4") (pin "3") (pinfunction "VCC_3") (pintype "passive"))
    )
    (net (code "106") (name "Net-(U5-B1)") (class "Default")
      (node (ref "RN3") (pin "1") (pintype "passive"))
      (node (ref "U5") (pin "21") (pinfunction "B1_21") (pintype "passive"))
    )
    (net (code "107") (name "Net-(U5-B2)") (class "Default")
      (node (ref "RN3") (pin "2") (pintype "passive"))
      (node (ref "U5") (pin "20") (pinfunction "B2_20") (pintype "passive"))
    )
    (net (code "108") (name "Net-(U5-B3)") (class "Default")
      (node (ref "RN3") (pin "3") (pintype "passive"))
      (node (ref "U5") (pin "19") (pinfunction "B3_19") (pintype "passive"))
    )
    (net (code "109") (name "Net-(U5-B4)") (class "Default")
      (node (ref "RN3") (pin "4") (pintype "passive"))
      (node (ref "U5") (pin "18") (pinfunction "B4_18") (pintype "passive"))
    )
    (net (code "110") (name "Net-(U5-B5)") (class "Default")
      (node (ref "RN4") (pin "1") (pintype "passive"))
      (node (ref "U5") (pin "17") (pinfunction "B5_17") (pintype "passive"))
    )
    (net (code "111") (name "Net-(U5-B6)") (class "Default")
      (node (ref "RN4") (pin "2") (pintype "passive"))
      (node (ref "U5") (pin "16") (pinfunction "B6_16") (pintype "passive"))
    )
    (net (code "112") (name "Net-(U5-B7)") (class "Default")
      (node (ref "RN4") (pin "3") (pintype "passive"))
      (node (ref "U5") (pin "15") (pinfunction "B7_15") (pintype "passive"))
    )
    (net (code "113") (name "Net-(U5-B8)") (class "Default")
      (node (ref "RN4") (pin "4") (pintype "passive"))
      (node (ref "U5") (pin "14") (pinfunction "B8_14") (pintype "passive"))
    )
    (net (code "114") (name "Net-(U6-VOUT)") (class "Default")
      (node (ref "C27") (pin "2") (pinfunction "2_2") (pintype "passive"))
      (node (ref "C28") (pin "2") (pinfunction "2_2") (pintype "passive"))
      (node (ref "L3") (pin "2") (pinfunction "2_2") (pintype "passive"))
      (node (ref "U6") (pin "2") (pinfunction "VOUT_2") (pintype "passive"))
    )
    (net (code "115") (name "Net-(U7-B1)") (class "Default")
      (node (ref "RN5") (pin "1") (pintype "passive"))
      (node (ref "U7") (pin "21") (pinfunction "B1_21") (pintype "passive"))
    )
    (net (code "116") (name "Net-(U7-B2)") (class "Default")
      (node (ref "RN5") (pin "2") (pintype "passive"))
      (node (ref "U7") (pin "20") (pinfunction "B2_20") (pintype "passive"))
    )
    (net (code "117") (name "Net-(U7-B3)") (class "Default")
      (node (ref "RN5") (pin "3") (pintype "passive"))
      (node (ref "U7") (pin "19") (pinfunction "B3_19") (pintype "passive"))
    )
    (net (code "118") (name "Net-(U7-B4)") (class "Default")
      (node (ref "RN5") (pin "4") (pintype "passive"))
      (node (ref "U7") (pin "18") (pinfunction "B4_18") (pintype "passive"))
    )
    (net (code "119") (name "Net-(U7-B5)") (class "Default")
      (node (ref "RN6") (pin "1") (pintype "passive"))
      (node (ref "U7") (pin "17") (pinfunction "B5_17") (pintype "passive"))
    )
    (net (code "120") (name "Net-(U7-B6)") (class "Default")
      (node (ref "RN6") (pin "2") (pintype "passive"))
      (node (ref "U7") (pin "16") (pinfunction "B6_16") (pintype "passive"))
    )
    (net (code "121") (name "Net-(U7-B7)") (class "Default")
      (node (ref "RN6") (pin "3") (pintype "passive"))
      (node (ref "U7") (pin "15") (pinfunction "B7_15") (pintype "passive"))
    )
    (net (code "122") (name "Net-(U7-B8)") (class "Default")
      (node (ref "RN6") (pin "4") (pintype "passive"))
      (node (ref "U7") (pin "14") (pinfunction "B8_14") (pintype "passive"))
    )
    (net (code "123") (name "Net-(U8-Y1)") (class "Default")
      (node (ref "R14") (pin "2") (pinfunction "2_2") (pintype "passive"))
      (node (ref "U8") (pin "6") (pinfunction "Y1_6") (pintype "passive"))
    )
    (net (code "124") (name "Net-(U8-Y2)") (class "Default")
      (node (ref "R15") (pin "2") (pinfunction "2_2") (pintype "passive"))
      (node (ref "U8") (pin "4") (pinfunction "Y2_4") (pintype "passive"))
    )
    (net (code "125") (name "Net-(U9-B1)") (class "Default")
      (node (ref "RN7") (pin "1") (pintype "passive"))
      (node (ref "U9") (pin "21") (pinfunction "B1_21") (pintype "passive"))
    )
    (net (code "126") (name "Net-(U9-B2)") (class "Default")
      (node (ref "RN7") (pin "2") (pintype "passive"))
      (node (ref "U9") (pin "20") (pinfunction "B2_20") (pintype "passive"))
    )
    (net (code "127") (name "Net-(U9-B3)") (class "Default")
      (node (ref "RN7") (pin "3") (pintype "passive"))
      (node (ref "U9") (pin "19") (pinfunction "B3_19") (pintype "passive"))
    )
    (net (code "128") (name "Net-(U9-B4)") (class "Default")
      (node (ref "RN7") (pin "4") (pintype "passive"))
      (node (ref "U9") (pin "18") (pinfunction "B4_18") (pintype "passive"))
    )
    (net (code "129") (name "Net-(U9-B5)") (class "Default")
      (node (ref "RN8") (pin "1") (pintype "passive"))
      (node (ref "U9") (pin "17") (pinfunction "B5_17") (pintype "passive"))
    )
    (net (code "130") (name "Net-(U9-B6)") (class "Default")
      (node (ref "RN8") (pin "2") (pintype "passive"))
      (node (ref "U9") (pin "16") (pinfunction "B6_16") (pintype "passive"))
    )
    (net (code "131") (name "Net-(U9-B7)") (class "Default")
      (node (ref "RN8") (pin "3") (pintype "passive"))
      (node (ref "U9") (pin "15") (pinfunction "B7_15") (pintype "passive"))
    )
    (net (code "132") (name "Net-(U9-B8)") (class "Default")
      (node (ref "RN8") (pin "4") (pintype "passive"))
      (node (ref "U9") (pin "14") (pinfunction "B8_14") (pintype "passive"))
    )
    (net (code "133") (name "VGND") (class "Default")
      (node (ref "C15") (pin "2") (pinfunction "2_2") (pintype "passive"))
      (node (ref "C19") (pin "1") (pinfunction "1_1") (pintype "passive"))
      (node (ref "C20") (pin "1") (pinfunction "1_1") (pintype "passive"))
      (node (ref "C21") (pin "1") (pinfunction "1_1") (pintype "passive"))
      (node (ref "L4") (pin "2") (pinfunction "2_2") (pintype "passive"))
      (node (ref "R11") (pin "1") (pinfunction "1_1") (pintype "passive"))
      (node (ref "R12") (pin "1") (pinfunction "1_1") (pintype "passive"))
      (node (ref "R13") (pin "1") (pinfunction "1_1") (pintype "passive"))
      (node (ref "R7") (pin "1") (pinfunction "1_1") (pintype "passive"))
      (node (ref "U3") (pin "1") (pinfunction "GND_1") (pintype "power_in"))
      (node (ref "U3") (pin "14") (pinfunction "GND_14") (pintype "power_in"))
      (node (ref "U3") (pin "15") (pinfunction "GND_15") (pintype "power_in"))
      (node (ref "U3") (pin "2") (pinfunction "GND_2") (pintype "power_in"))
      (node (ref "U3") (pin "25") (pinfunction "GND_25") (pintype "power_in"))
      (node (ref "U3") (pin "26") (pinfunction "GND_26") (pintype "power_in"))
      (node (ref "U3") (pin "27") (pinfunction "~{IOB}_27") (pintype "input"))
      (node (ref "U3") (pin "31") (pinfunction "~{IOG}_31") (pintype "input"))
      (node (ref "U3") (pin "33") (pinfunction "~{IOR}_33") (pintype "input"))
      (node (ref "U3") (pin "39") (pinfunction "GND_39") (pintype "power_in"))
      (node (ref "U3") (pin "40") (pinfunction "GND_40") (pintype "power_in"))
    )
    (net (code "134") (name "VIO") (class "Default")
      (node (ref "C24") (pin "2") (pinfunction "2_2") (pintype "passive"))
      (node (ref "C32") (pin "2") (pinfunction "2_2") (pintype "passive"))
      (node (ref "C37") (pin "2") (pinfunction "2_2") (pintype "passive"))
      (node (ref "C39") (pin "2") (pinfunction "2_2") (pintype "passive"))
      (node (ref "U2") (pin "1") (pinfunction "VCCA_1") (pintype "power_in"))
      (node (ref "U2") (pin "2") (pinfunction "DIR_2") (pintype "input"))
      (node (ref "U5") (pin "1") (pinfunction "VCCA_1") (pintype "power_in"))
      (node (ref "U5") (pin "2") (pinfunction "DIR_2") (pintype "input"))
      (node (ref "U7") (pin "1") (pinfunction "VCCA_1") (pintype "power_in"))
      (node (ref "U7") (pin "2") (pinfunction "DIR_2") (pintype "input"))
      (node (ref "U9") (pin "1") (pinfunction "VCCA_1") (pintype "power_in"))
      (node (ref "U9") (pin "2") (pinfunction "DIR_2") (pintype "input"))
    )
    (net (code "135") (name "VLCD") (class "Default")
      (node (ref "C15") (pin "1") (pinfunction "1_1") (pintype "passive"))
      (node (ref "C16") (pin "2") (pinfunction "2_2") (pintype "passive"))
      (node (ref "C23") (pin "2") (pinfunction "2_2") (pintype "passive"))
      (node (ref "C31") (pin "2") (pinfunction "2_2") (pintype "passive"))
      (node (ref "C36") (pin "2") (pinfunction "2_2") (pintype "passive"))
      (node (ref "C38") (pin "2") (pinfunction "2_2") (pintype "passive"))
      (node (ref "H5") (pin "28") (pinfunction "28_28") (pintype "passive"))
      (node (ref "L1") (pin "1") (pinfunction "1_1") (pintype "passive"))
      (node (ref "L2") (pin "2") (pinfunction "2_2") (pintype "passive"))
      (node (ref "U2") (pin "23") (pinfunction "VCCB_23") (pintype "power_in"))
      (node (ref "U2") (pin "24") (pinfunction "VCCB_24") (pintype "power_in"))
      (node (ref "U5") (pin "23") (pinfunction "VCCB_23") (pintype "power_in"))
      (node (ref "U5") (pin "24") (pinfunction "VCCB_24") (pintype "power_in"))
      (node (ref "U7") (pin "23") (pinfunction "VCCB_23") (pintype "power_in"))
      (node (ref "U7") (pin "24") (pinfunction "VCCB_24") (pintype "power_in"))
      (node (ref "U9") (pin "23") (pinfunction "VCCB_23") (pintype "power_in"))
      (node (ref "U9") (pin "24") (pinfunction "VCCB_24") (pintype "power_in"))
    )
    (net (code "136") (name "VSB") (class "Default")
      (node (ref "C13") (pin "2") (pinfunction "2_2") (pintype "passive"))
      (node (ref "R5") (pin "2") (pinfunction "2_2") (pintype "passive"))
      (node (ref "R6") (pin "1") (pinfunction "1_1") (pintype "passive"))
      (node (ref "R8") (pin "1") (pinfunction "1_1") (pintype "passive"))
      (node (ref "T1") (pin "1") (pinfunction "G_1") (pintype "passive"))
    )
    (net (code "137") (name "VVGA") (class "Default")
      (node (ref "C17") (pin "2") (pinfunction "2_2") (pintype "passive"))
      (node (ref "C18") (pin "2") (pinfunction "2_2") (pintype "passive"))
      (node (ref "C19") (pin "2") (pinfunction "2_2") (pintype "passive"))
      (node (ref "C20") (pin "2") (pinfunction "2_2") (pintype "passive"))
      (node (ref "C21") (pin "2") (pinfunction "2_2") (pintype "passive"))
      (node (ref "L2") (pin "1") (pinfunction "1_1") (pintype "passive"))
      (node (ref "L3") (pin "1") (pinfunction "1_1") (pintype "passive"))
      (node (ref "U3") (pin "13") (pinfunction "VAA_13") (pintype "power_in"))
      (node (ref "U3") (pin "29") (pinfunction "VAA_29") (pintype "power_in"))
      (node (ref "U3") (pin "30") (pinfunction "VAA_30") (pintype "power_in"))
    )
    (net (code "138") (name "unconnected-(U1-IREDC-Pad2)") (class "Default")
      (node (ref "U1") (pin "2") (pinfunction "IREDC_2") (pintype "passive+no_connect"))
    )
    (net (code "139") (name "unconnected-(U1-NC-Pad7)") (class "Default")
      (node (ref "U1") (pin "7") (pinfunction "NC_7") (pintype "passive+no_connect"))
    )
  )
)
